# GP4SF1109F2.net
KiCad netlist of a schematic drawn in EAGLE
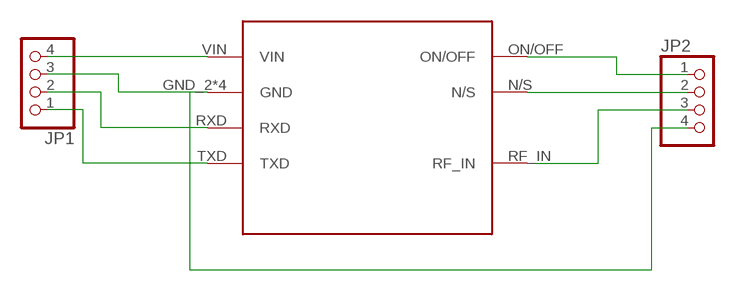
[diagram p0: schematic, sheet 1]

(export (version "E")
  (design (tool "Eeschema 10.0.6"))
  (components
    (comp (ref "JP1")
      (value "PINHD-1X4")
      (footprint "eagle-import:1X04")
      (libsource (lib "eagle-import") (part "PINHD-1X4"))
    )
    (comp (ref "JP2")
      (value "PINHD-1X4")
      (footprint "eagle-import:1X04")
      (libsource (lib "eagle-import") (part "PINHD-1X4"))
    )
    (comp (ref "U$1")
      (value "GP4SF1109F2")
      (footprint "eagle-import:GP4SF1109F2")
      (libsource (lib "eagle-import") (part "GP4SF1109F2"))
    )
  )
  (nets
    (net (code "1") (name "Net-(JP1-Pad1)") (class "Default")
      (node (ref "JP1") (pin "1") (pinfunction "1_1") (pintype "passive"))
      (node (ref "U$1") (pin "TXD") (pinfunction "TXD_TXD") (pintype "bidirectional"))
    )
    (net (code "2") (name "Net-(JP1-Pad2)") (class "Default")
      (node (ref "JP1") (pin "2") (pinfunction "2_2") (pintype "passive"))
      (node (ref "U$1") (pin "RXD") (pinfunction "RXD_RXD") (pintype "bidirectional"))
    )
    (net (code "3") (name "Net-(JP1-Pad3)") (class "Default")
      (node (ref "JP1") (pin "3") (pinfunction "3_3") (pintype "passive"))
      (node (ref "JP2") (pin "4") (pinfunction "4_4") (pintype "passive"))
      (node (ref "U$1") (pin "GND_2") (pinfunction "GND_GND_2") (pintype "bidirectional"))
      (node (ref "U$1") (pin "GND_5") (pinfunction "GND_GND_5") (pintype "bidirectional"))
      (node (ref "U$1") (pin "GND_6") (pinfunction "GND_GND_6") (pintype "bidirectional"))
      (node (ref "U$1") (pin "GND_8") (pinfunction "GND_GND_8") (pintype "bidirectional"))
    )
    (net (code "4") (name "Net-(JP1-Pad4)") (class "Default")
      (node (ref "JP1") (pin "4") (pinfunction "4_4") (pintype "passive"))
      (node (ref "U$1") (pin "VIN") (pinfunction "VIN_VIN") (pintype "bidirectional"))
    )
    (net (code "5") (name "Net-(JP2-Pad1)") (class "Default")
      (node (ref "JP2") (pin "1") (pinfunction "1_1") (pintype "passive"))
      (node (ref "U$1") (pin "ON/OFF") (pinfunction "ON/OFF_ON/OFF") (pintype "bidirectional"))
    )
    (net (code "6") (name "Net-(JP2-Pad2)") (class "Default")
      (node (ref "JP2") (pin "2") (pinfunction "2_2") (pintype "passive"))
      (node (ref "U$1") (pin "N/S") (pinfunction "N/S_N/S") (pintype "bidirectional"))
    )
    (net (code "7") (name "Net-(JP2-Pad3)") (class "Default")
      (node (ref "JP2") (pin "3") (pinfunction "3_3") (pintype "passive"))
      (node (ref "U$1") (pin "RF_IN") (pinfunction "RF_IN_RF_IN") (pintype "bidirectional"))
    )
  )
)
